# Ananas-core-0_9_2.net
KiCad netlist of a schematic drawn in EAGLE
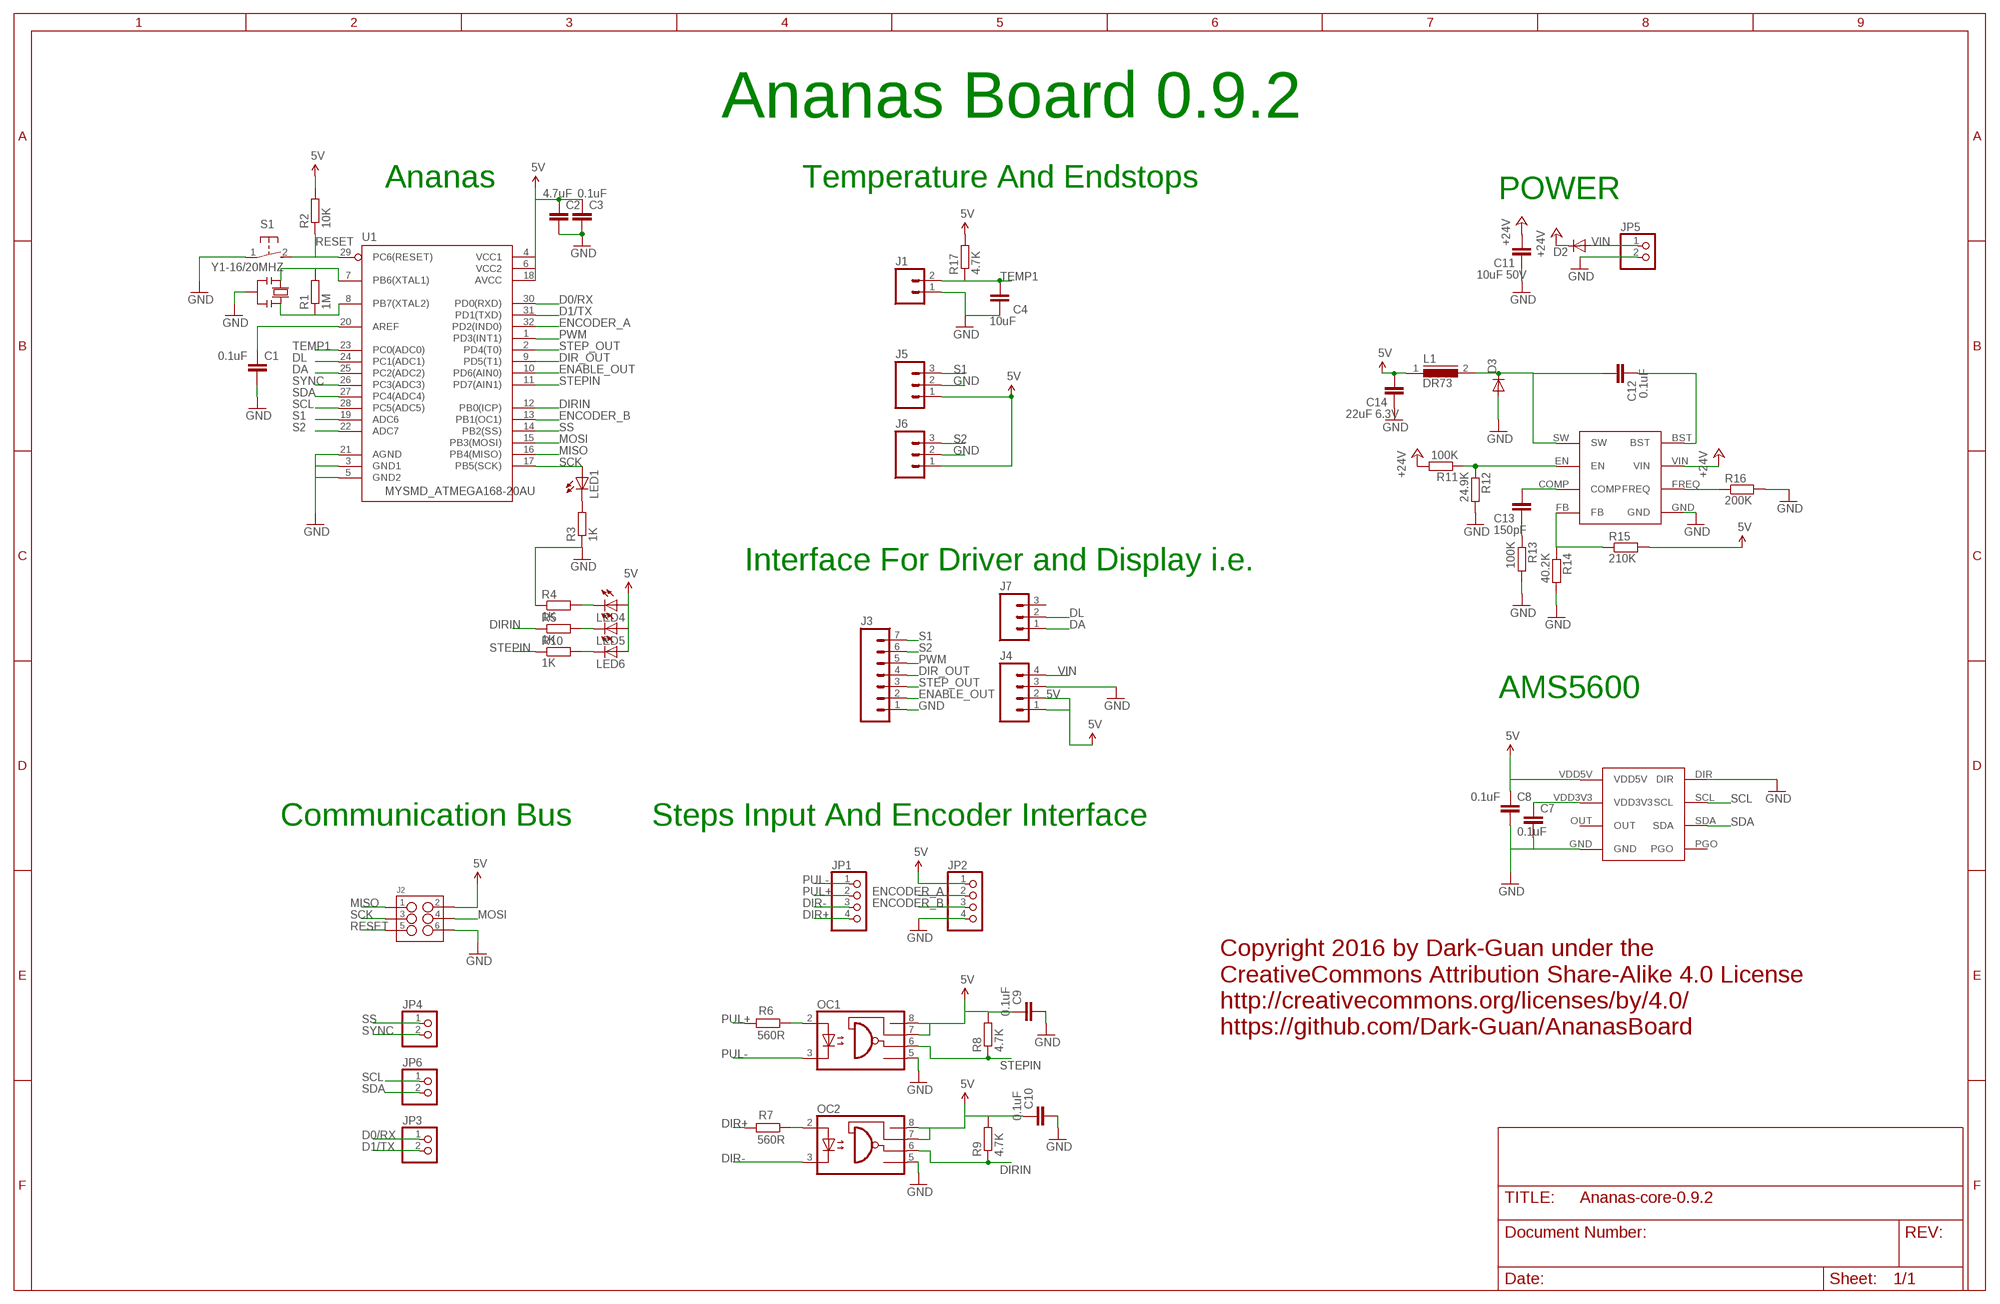
[diagram p0: schematic, sheet 1]

(export (version "E")
  (design (tool "Eeschema 10.0.6"))
  (components
    (comp (ref "C1")
      (value "0.1uF")
      (footprint "eagle-import:C0603K")
      (libsource (lib "eagle-import") (part "C-EUC0603K"))
    )
    (comp (ref "C2")
      (value "4.7uF")
      (footprint "eagle-import:C0603K")
      (libsource (lib "eagle-import") (part "C-EUC0603K"))
    )
    (comp (ref "C3")
      (value "0.1uF")
      (footprint "eagle-import:C0603K")
      (libsource (lib "eagle-import") (part "C-EUC0603K"))
    )
    (comp (ref "C4")
      (value "10uF")
      (footprint "eagle-import:C0603K")
      (libsource (lib "eagle-import") (part "C-EUC0603K"))
    )
    (comp (ref "C7")
      (value "0.1uF")
      (footprint "eagle-import:C0603K")
      (libsource (lib "eagle-import") (part "C-EUC0603K"))
    )
    (comp (ref "C8")
      (value "0.1uF")
      (footprint "eagle-import:C0603K")
      (libsource (lib "eagle-import") (part "C-EUC0603K"))
    )
    (comp (ref "C9")
      (value "0.1uF")
      (footprint "eagle-import:C0603K")
      (libsource (lib "eagle-import") (part "C-EUC0603K"))
    )
    (comp (ref "C10")
      (value "0.1uF")
      (footprint "eagle-import:C0603K")
      (libsource (lib "eagle-import") (part "C-EUC0603K"))
    )
    (comp (ref "C11")
      (value "10uF 50V")
      (footprint "eagle-import:C0805")
      (libsource (lib "eagle-import") (part "C-EUC0805"))
    )
    (comp (ref "C12")
      (value "0.1uF")
      (footprint "eagle-import:C0603K")
      (libsource (lib "eagle-import") (part "C-EUC0603K"))
    )
    (comp (ref "C13")
      (value "150pF")
      (footprint "eagle-import:C0603K")
      (libsource (lib "eagle-import") (part "C-EUC0603K"))
    )
    (comp (ref "C14")
      (value "22uF 6.3V")
      (footprint "eagle-import:C0805")
      (libsource (lib "eagle-import") (part "C-EUC0805"))
    )
    (comp (ref "D2")
      (value "DIODE_DIODE-SMB")
      (footprint "eagle-import:DIODE_SMB")
      (libsource (lib "eagle-import") (part "DIODE_DIODE-SMB"))
    )
    (comp (ref "D3")
      (value "DIODE_DIODE-SMB")
      (footprint "eagle-import:DIODE_SMB")
      (libsource (lib "eagle-import") (part "DIODE_DIODE-SMB"))
    )
    (comp (ref "J1")
      (value "M02PTH")
      (footprint "eagle-import:1X02")
      (libsource (lib "eagle-import") (part "M02PTH"))
    )
    (comp (ref "J2")
      (value "M03X2NO_SILK")
      (footprint "eagle-import:2X3-NS")
      (libsource (lib "eagle-import") (part "M03X2NO_SILK"))
    )
    (comp (ref "J3")
      (value "M07")
      (footprint "eagle-import:1X07")
      (libsource (lib "eagle-import") (part "M07"))
    )
    (comp (ref "J4")
      (value "M04PTH")
      (footprint "eagle-import:1X04")
      (libsource (lib "eagle-import") (part "M04PTH"))
    )
    (comp (ref "J5")
      (value "M03PTH")
      (footprint "eagle-import:1X03")
      (libsource (lib "eagle-import") (part "M03PTH"))
    )
    (comp (ref "J6")
      (value "M03PTH")
      (footprint "eagle-import:1X03")
      (libsource (lib "eagle-import") (part "M03PTH"))
    )
    (comp (ref "J7")
      (value "M03PTH")
      (footprint "eagle-import:1X03")
      (libsource (lib "eagle-import") (part "M03PTH"))
    )
    (comp (ref "JP1")
      (value "PINHD-1X4/OCT")
      (footprint "eagle-import:1X04_OCT")
      (libsource (lib "eagle-import") (part "PINHD-1X4/OCT"))
    )
    (comp (ref "JP2")
      (value "PINHD-1X4/OCT")
      (footprint "eagle-import:1X04_OCT")
      (libsource (lib "eagle-import") (part "PINHD-1X4/OCT"))
    )
    (comp (ref "JP3")
      (value "PINHD-1X2/OCT")
      (footprint "eagle-import:1X02_OCT")
      (libsource (lib "eagle-import") (part "PINHD-1X2/OCT"))
    )
    (comp (ref "JP4")
      (value "PINHD-1X2/OCT")
      (footprint "eagle-import:1X02_OCT")
      (libsource (lib "eagle-import") (part "PINHD-1X2/OCT"))
    )
    (comp (ref "JP5")
      (value "PINHD-1X2/OCT")
      (footprint "eagle-import:1X02_OCT")
      (libsource (lib "eagle-import") (part "PINHD-1X2/OCT"))
    )
    (comp (ref "JP6")
      (value "PINHD-1X2/OCT")
      (footprint "eagle-import:1X02_OCT")
      (libsource (lib "eagle-import") (part "PINHD-1X2/OCT"))
    )
    (comp (ref "L1")
      (value "DR73")
      (footprint "eagle-import:DR73")
      (libsource (lib "eagle-import") (part "DR73"))
    )
    (comp (ref "LED1")
      (value "LEDCHIPLED_0603")
      (footprint "eagle-import:CHIPLED_0603")
      (libsource (lib "eagle-import") (part "LEDCHIPLED_0603"))
    )
    (comp (ref "LED4")
      (value "LEDCHIPLED_0603")
      (footprint "eagle-import:CHIPLED_0603")
      (libsource (lib "eagle-import") (part "LEDCHIPLED_0603"))
    )
    (comp (ref "LED5")
      (value "LEDCHIPLED_0603")
      (footprint "eagle-import:CHIPLED_0603")
      (libsource (lib "eagle-import") (part "LEDCHIPLED_0603"))
    )
    (comp (ref "LED6")
      (value "LEDCHIPLED_0603")
      (footprint "eagle-import:CHIPLED_0603")
      (libsource (lib "eagle-import") (part "LEDCHIPLED_0603"))
    )
    (comp (ref "MP1854")
      (value "MP1584")
      (footprint "eagle-import:MP1584")
      (libsource (lib "eagle-import") (part "MP1584"))
    )
    (comp (ref "OC1")
      (value "OPTOCOUPLER_(2)_HCPL0600")
      (footprint "eagle-import:OPTOCOUPLER_(2)_SOIC08")
      (libsource (lib "eagle-import") (part "OPTOCOUPLER_(2)_HCPL0600"))
    )
    (comp (ref "OC2")
      (value "OPTOCOUPLER_(2)_HCPL0600")
      (footprint "eagle-import:OPTOCOUPLER_(2)_SOIC08")
      (libsource (lib "eagle-import") (part "OPTOCOUPLER_(2)_HCPL0600"))
    )
    (comp (ref "R1")
      (value "1M")
      (footprint "eagle-import:R0603")
      (libsource (lib "eagle-import") (part "R-EU_R0603"))
    )
    (comp (ref "R2")
      (value "10K")
      (footprint "eagle-import:R0603")
      (libsource (lib "eagle-import") (part "R-EU_R0603"))
    )
    (comp (ref "R3")
      (value "1K")
      (footprint "eagle-import:R0603")
      (libsource (lib "eagle-import") (part "R-EU_R0603"))
    )
    (comp (ref "R4")
      (value "1K")
      (footprint "eagle-import:R0603")
      (libsource (lib "eagle-import") (part "R-EU_R0603"))
    )
    (comp (ref "R5")
      (value "1K")
      (footprint "eagle-import:R0603")
      (libsource (lib "eagle-import") (part "R-EU_R0603"))
    )
    (comp (ref "R6")
      (value "560R")
      (footprint "eagle-import:R0603")
      (libsource (lib "eagle-import") (part "R-EU_R0603"))
    )
    (comp (ref "R7")
      (value "560R")
      (footprint "eagle-import:R0603")
      (libsource (lib "eagle-import") (part "R-EU_R0603"))
    )
    (comp (ref "R8")
      (value "4.7K")
      (footprint "eagle-import:R0603")
      (libsource (lib "eagle-import") (part "R-EU_R0603"))
    )
    (comp (ref "R9")
      (value "4.7K")
      (footprint "eagle-import:R0603")
      (libsource (lib "eagle-import") (part "R-EU_R0603"))
    )
    (comp (ref "R10")
      (value "1K")
      (footprint "eagle-import:R0603")
      (libsource (lib "eagle-import") (part "R-EU_R0603"))
    )
    (comp (ref "R11")
      (value "100K")
      (footprint "eagle-import:R0603")
      (libsource (lib "eagle-import") (part "R-EU_R0603"))
    )
    (comp (ref "R12")
      (value "24.9K")
      (footprint "eagle-import:R0603")
      (libsource (lib "eagle-import") (part "R-EU_R0603"))
    )
    (comp (ref "R13")
      (value "100K")
      (footprint "eagle-import:R0603")
      (libsource (lib "eagle-import") (part "R-EU_R0603"))
    )
    (comp (ref "R14")
      (value "40.2K")
      (footprint "eagle-import:R0603")
      (libsource (lib "eagle-import") (part "R-EU_R0603"))
    )
    (comp (ref "R15")
      (value "210K")
      (footprint "eagle-import:R0603")
      (libsource (lib "eagle-import") (part "R-EU_R0603"))
    )
    (comp (ref "R16")
      (value "200K")
      (footprint "eagle-import:R0603")
      (libsource (lib "eagle-import") (part "R-EU_R0603"))
    )
    (comp (ref "R17")
      (value "4.7K")
      (footprint "eagle-import:R0603")
      (libsource (lib "eagle-import") (part "R-EU_R0603"))
    )
    (comp (ref "S1")
      (value "31-XX")
      (footprint "eagle-import:B3F-31XX")
      (fields (field (name "MPN") "B3F-3100"))
      (libsource (lib "eagle-import") (part "31-XX"))
    )
    (comp (ref "U$1")
      (value "ARDUINO_AS5600")
      (footprint "eagle-import:ARDUINO_AS5600")
      (libsource (lib "eagle-import") (part "ARDUINO_AS5600"))
    )
    (comp (ref "U1")
      (value "MYSMD_ATMEGA168-20AU")
      (footprint "eagle-import:MYSMD_QFP032")
      (libsource (lib "eagle-import") (part "MYSMD_ATMEGA168-20AU"))
    )
    (comp (ref "Y1-16/20MHZ")
      (value "MYSMD2_RESONATORMU")
      (footprint "eagle-import:MYSMD2_RESONATOR")
      (libsource (lib "eagle-import") (part "MYSMD2_RESONATORMU"))
    )
  )
  (nets
    (net (code "1") (name "+24V") (class "Default")
      (node (ref "C11") (pin "2") (pinfunction "2_2") (pintype "passive"))
      (node (ref "D2") (pin "C") (pinfunction "C_C") (pintype "passive"))
      (node (ref "MP1854") (pin "VIN") (pinfunction "VIN_VIN") (pintype "bidirectional"))
      (node (ref "R11") (pin "2") (pinfunction "2_2") (pintype "passive"))
    )
    (net (code "2") (name "/D0{slash}RX") (class "Default")
      (node (ref "JP3") (pin "1") (pinfunction "1_1") (pintype "passive"))
      (node (ref "U1") (pin "30") (pinfunction "PD0(RXD)_30") (pintype "bidirectional"))
    )
    (net (code "3") (name "/D1{slash}TX") (class "Default")
      (node (ref "JP3") (pin "2") (pinfunction "2_2") (pintype "passive"))
      (node (ref "U1") (pin "31") (pinfunction "PD1(TXD)_31") (pintype "bidirectional"))
    )
    (net (code "4") (name "/DA") (class "Default")
      (node (ref "J7") (pin "1") (pinfunction "1_1") (pintype "passive"))
      (node (ref "U1") (pin "25") (pinfunction "PC2(ADC2)_25") (pintype "passive"))
    )
    (net (code "5") (name "/DIR+") (class "Default")
      (node (ref "JP1") (pin "4") (pinfunction "4_4") (pintype "passive"))
      (node (ref "R7") (pin "2") (pinfunction "2_2") (pintype "passive"))
    )
    (net (code "6") (name "/DIR-") (class "Default")
      (node (ref "JP1") (pin "3") (pinfunction "3_3") (pintype "passive"))
      (node (ref "OC2") (pin "3") (pinfunction "C_3") (pintype "passive"))
    )
    (net (code "7") (name "/DIRIN") (class "Default")
      (node (ref "OC2") (pin "6") (pinfunction "VO_6") (pintype "passive"))
      (node (ref "R5") (pin "1") (pinfunction "1_1") (pintype "passive"))
      (node (ref "R9") (pin "1") (pinfunction "1_1") (pintype "passive"))
      (node (ref "U1") (pin "12") (pinfunction "PB0(ICP)_12") (pintype "bidirectional"))
    )
    (net (code "8") (name "/DIR_OUT") (class "Default")
      (node (ref "J3") (pin "4") (pinfunction "4_4") (pintype "passive"))
      (node (ref "U1") (pin "9") (pinfunction "PD5(T1)_9") (pintype "bidirectional"))
    )
    (net (code "9") (name "/DL") (class "Default")
      (node (ref "J7") (pin "2") (pinfunction "2_2") (pintype "passive"))
      (node (ref "U1") (pin "24") (pinfunction "PC1(ADC1)_24") (pintype "passive"))
    )
    (net (code "10") (name "/ENABLE_OUT") (class "Default")
      (node (ref "J3") (pin "2") (pinfunction "2_2") (pintype "passive"))
      (node (ref "U1") (pin "10") (pinfunction "PD6(AIN0)_10") (pintype "bidirectional"))
    )
    (net (code "11") (name "/ENCODER_A") (class "Default")
      (node (ref "JP2") (pin "2") (pinfunction "2_2") (pintype "passive"))
      (node (ref "U1") (pin "32") (pinfunction "PD2(IND0)_32") (pintype "bidirectional"))
    )
    (net (code "12") (name "/ENCODER_B") (class "Default")
      (node (ref "JP2") (pin "3") (pinfunction "3_3") (pintype "passive"))
      (node (ref "U1") (pin "13") (pinfunction "PB1(OC1)_13") (pintype "bidirectional"))
    )
    (net (code "13") (name "/MISO") (class "Default")
      (node (ref "J2") (pin "1") (pinfunction "1_1") (pintype "bidirectional"))
      (node (ref "U1") (pin "16") (pinfunction "PB4(MISO)_16") (pintype "bidirectional"))
    )
    (net (code "14") (name "/MOSI") (class "Default")
      (node (ref "J2") (pin "4") (pinfunction "4_4") (pintype "bidirectional"))
      (node (ref "U1") (pin "15") (pinfunction "PB3(MOSI)_15") (pintype "bidirectional"))
    )
    (net (code "15") (name "/PUL+") (class "Default")
      (node (ref "JP1") (pin "2") (pinfunction "2_2") (pintype "passive"))
      (node (ref "R6") (pin "2") (pinfunction "2_2") (pintype "passive"))
    )
    (net (code "16") (name "/PUL-") (class "Default")
      (node (ref "JP1") (pin "1") (pinfunction "1_1") (pintype "passive"))
      (node (ref "OC1") (pin "3") (pinfunction "C_3") (pintype "passive"))
    )
    (net (code "17") (name "/PWM") (class "Default")
      (node (ref "J3") (pin "5") (pinfunction "5_5") (pintype "passive"))
      (node (ref "U1") (pin "1") (pinfunction "PD3(INT1)_1") (pintype "bidirectional"))
    )
    (net (code "18") (name "/RESET") (class "Default")
      (node (ref "J2") (pin "5") (pinfunction "5_5") (pintype "bidirectional"))
      (node (ref "R2") (pin "1") (pinfunction "1_1") (pintype "passive"))
      (node (ref "S1") (pin "2") (pinfunction "S_2") (pintype "passive"))
      (node (ref "U1") (pin "29") (pinfunction "PC6(RESET)_29") (pintype "bidirectional"))
    )
    (net (code "19") (name "/S1") (class "Default")
      (node (ref "J3") (pin "7") (pinfunction "7_7") (pintype "passive"))
      (node (ref "J5") (pin "3") (pinfunction "3_3") (pintype "passive"))
      (node (ref "U1") (pin "19") (pinfunction "ADC6_19") (pintype "passive"))
    )
    (net (code "20") (name "/S2") (class "Default")
      (node (ref "J3") (pin "6") (pinfunction "6_6") (pintype "passive"))
      (node (ref "J6") (pin "3") (pinfunction "3_3") (pintype "passive"))
      (node (ref "U1") (pin "22") (pinfunction "ADC7_22") (pintype "passive"))
    )
    (net (code "21") (name "/SCK") (class "Default")
      (node (ref "J2") (pin "3") (pinfunction "3_3") (pintype "bidirectional"))
      (node (ref "LED1") (pin "A") (pinfunction "A_A") (pintype "passive"))
      (node (ref "U1") (pin "17") (pinfunction "PB5(SCK)_17") (pintype "bidirectional"))
    )
    (net (code "22") (name "/SCL") (class "Default")
      (node (ref "JP6") (pin "1") (pinfunction "1_1") (pintype "passive"))
      (node (ref "U$1") (pin "SCL") (pinfunction "SCL_SCL") (pintype "bidirectional"))
      (node (ref "U1") (pin "28") (pinfunction "PC5(ADC5)_28") (pintype "passive"))
    )
    (net (code "23") (name "/SDA") (class "Default")
      (node (ref "JP6") (pin "2") (pinfunction "2_2") (pintype "passive"))
      (node (ref "U$1") (pin "SDA") (pinfunction "SDA_SDA") (pintype "bidirectional"))
      (node (ref "U1") (pin "27") (pinfunction "PC4(ADC4)_27") (pintype "passive"))
    )
    (net (code "24") (name "/SS") (class "Default")
      (node (ref "JP4") (pin "1") (pinfunction "1_1") (pintype "passive"))
      (node (ref "U1") (pin "14") (pinfunction "PB2(SS)_14") (pintype "bidirectional"))
    )
    (net (code "25") (name "/STEPIN") (class "Default")
      (node (ref "OC1") (pin "6") (pinfunction "VO_6") (pintype "passive"))
      (node (ref "R10") (pin "1") (pinfunction "1_1") (pintype "passive"))
      (node (ref "R8") (pin "1") (pinfunction "1_1") (pintype "passive"))
      (node (ref "U1") (pin "11") (pinfunction "PD7(AIN1)_11") (pintype "bidirectional"))
    )
    (net (code "26") (name "/STEP_OUT") (class "Default")
      (node (ref "J3") (pin "3") (pinfunction "3_3") (pintype "passive"))
      (node (ref "U1") (pin "2") (pinfunction "PD4(T0)_2") (pintype "bidirectional"))
    )
    (net (code "27") (name "/SYNC") (class "Default")
      (node (ref "JP4") (pin "2") (pinfunction "2_2") (pintype "passive"))
      (node (ref "U1") (pin "26") (pinfunction "PC3(ADC3)_26") (pintype "passive"))
    )
    (net (code "28") (name "/TEMP1") (class "Default")
      (node (ref "C4") (pin "2") (pinfunction "2_2") (pintype "passive"))
      (node (ref "J1") (pin "2") (pinfunction "2_2") (pintype "passive"))
      (node (ref "R17") (pin "1") (pinfunction "1_1") (pintype "passive"))
      (node (ref "U1") (pin "23") (pinfunction "PC0(ADC0)_23") (pintype "passive"))
    )
    (net (code "29") (name "/VIN") (class "Default")
      (node (ref "D2") (pin "A") (pinfunction "A_A") (pintype "passive"))
      (node (ref "J4") (pin "4") (pinfunction "4_4") (pintype "passive"))
      (node (ref "JP5") (pin "1") (pinfunction "1_1") (pintype "passive"))
    )
    (net (code "30") (name "5V") (class "Default")
      (node (ref "C10") (pin "1") (pinfunction "1_1") (pintype "passive"))
      (node (ref "C14") (pin "2") (pinfunction "2_2") (pintype "passive"))
      (node (ref "C2") (pin "1") (pinfunction "1_1") (pintype "passive"))
      (node (ref "C3") (pin "1") (pinfunction "1_1") (pintype "passive"))
      (node (ref "C8") (pin "1") (pinfunction "1_1") (pintype "passive"))
      (node (ref "C9") (pin "1") (pinfunction "1_1") (pintype "passive"))
      (node (ref "J2") (pin "2") (pinfunction "2_2") (pintype "bidirectional"))
      (node (ref "J4") (pin "1") (pinfunction "1_1") (pintype "passive"))
      (node (ref "J4") (pin "2") (pinfunction "2_2") (pintype "passive"))
      (node (ref "J5") (pin "1") (pinfunction "1_1") (pintype "passive"))
      (node (ref "J6") (pin "1") (pinfunction "1_1") (pintype "passive"))
      (node (ref "JP2") (pin "1") (pinfunction "1_1") (pintype "passive"))
      (node (ref "L1") (pin "1") (pinfunction "1_1") (pintype "passive"))
      (node (ref "LED4") (pin "A") (pinfunction "A_A") (pintype "passive"))
      (node (ref "LED5") (pin "A") (pinfunction "A_A") (pintype "passive"))
      (node (ref "LED6") (pin "A") (pinfunction "A_A") (pintype "passive"))
      (node (ref "OC1") (pin "7") (pinfunction "VE_7") (pintype "passive"))
      (node (ref "OC1") (pin "8") (pinfunction "VCC_8") (pintype "passive"))
      (node (ref "OC2") (pin "7") (pinfunction "VE_7") (pintype "passive"))
      (node (ref "OC2") (pin "8") (pinfunction "VCC_8") (pintype "passive"))
      (node (ref "R15") (pin "2") (pinfunction "2_2") (pintype "passive"))
      (node (ref "R17") (pin "2") (pinfunction "2_2") (pintype "passive"))
      (node (ref "R2") (pin "2") (pinfunction "2_2") (pintype "passive"))
      (node (ref "R8") (pin "2") (pinfunction "2_2") (pintype "passive"))
      (node (ref "R9") (pin "2") (pinfunction "2_2") (pintype "passive"))
      (node (ref "U$1") (pin "VDD5V") (pinfunction "VDD5V_VDD5V") (pintype "bidirectional"))
      (node (ref "U1") (pin "18") (pinfunction "AVCC_18") (pintype "passive"))
      (node (ref "U1") (pin "4") (pinfunction "VCC1_4") (pintype "power_in"))
      (node (ref "U1") (pin "6") (pinfunction "VCC2_6") (pintype "power_in"))
    )
    (net (code "31") (name "GND") (class "Default")
      (node (ref "C1") (pin "2") (pinfunction "2_2") (pintype "passive"))
      (node (ref "C10") (pin "2") (pinfunction "2_2") (pintype "passive"))
      (node (ref "C11") (pin "1") (pinfunction "1_1") (pintype "passive"))
      (node (ref "C14") (pin "1") (pinfunction "1_1") (pintype "passive"))
      (node (ref "C2") (pin "2") (pinfunction "2_2") (pintype "passive"))
      (node (ref "C3") (pin "2") (pinfunction "2_2") (pintype "passive"))
      (node (ref "C4") (pin "1") (pinfunction "1_1") (pintype "passive"))
      (node (ref "C7") (pin "2") (pinfunction "2_2") (pintype "passive"))
      (node (ref "C8") (pin "2") (pinfunction "2_2") (pintype "passive"))
      (node (ref "C9") (pin "2") (pinfunction "2_2") (pintype "passive"))
      (node (ref "D3") (pin "A") (pinfunction "A_A") (pintype "passive"))
      (node (ref "J1") (pin "1") (pinfunction "1_1") (pintype "passive"))
      (node (ref "J2") (pin "6") (pinfunction "6_6") (pintype "bidirectional"))
      (node (ref "J3") (pin "1") (pinfunction "1_1") (pintype "passive"))
      (node (ref "J4") (pin "3") (pinfunction "3_3") (pintype "passive"))
      (node (ref "J5") (pin "2") (pinfunction "2_2") (pintype "passive"))
      (node (ref "J6") (pin "2") (pinfunction "2_2") (pintype "passive"))
      (node (ref "JP2") (pin "4") (pinfunction "4_4") (pintype "passive"))
      (node (ref "JP5") (pin "2") (pinfunction "2_2") (pintype "passive"))
      (node (ref "MP1854") (pin "GND") (pinfunction "GND_GND") (pintype "bidirectional"))
      (node (ref "OC1") (pin "5") (pinfunction "GND_5") (pintype "passive"))
      (node (ref "OC2") (pin "5") (pinfunction "GND_5") (pintype "passive"))
      (node (ref "R12") (pin "2") (pinfunction "2_2") (pintype "passive"))
      (node (ref "R13") (pin "2") (pinfunction "2_2") (pintype "passive"))
      (node (ref "R14") (pin "2") (pinfunction "2_2") (pintype "passive"))
      (node (ref "R16") (pin "2") (pinfunction "2_2") (pintype "passive"))
      (node (ref "R3") (pin "1") (pinfunction "1_1") (pintype "passive"))
      (node (ref "R4") (pin "1") (pinfunction "1_1") (pintype "passive"))
      (node (ref "S1") (pin "1") (pinfunction "P_1") (pintype "passive"))
      (node (ref "U$1") (pin "DIR") (pinfunction "DIR_DIR") (pintype "bidirectional"))
      (node (ref "U$1") (pin "GND") (pinfunction "GND_GND") (pintype "bidirectional"))
      (node (ref "U1") (pin "21") (pinfunction "AGND_21") (pintype "passive"))
      (node (ref "U1") (pin "3") (pinfunction "GND1_3") (pintype "power_in"))
      (node (ref "U1") (pin "5") (pinfunction "GND2_5") (pintype "power_in"))
      (node (ref "Y1-16/20MHZ") (pin "2") (pinfunction "2_2") (pintype "passive"))
    )
    (net (code "32") (name "Net-(C7-Pad1)") (class "Default")
      (node (ref "C7") (pin "1") (pinfunction "1_1") (pintype "passive"))
      (node (ref "U$1") (pin "VDD3V3") (pinfunction "VDD3V3_VDD3V3") (pintype "bidirectional"))
    )
    (net (code "33") (name "Net-(C12-Pad1)") (class "Default")
      (node (ref "C12") (pin "1") (pinfunction "1_1") (pintype "passive"))
      (node (ref "MP1854") (pin "BST") (pinfunction "BST_BST") (pintype "bidirectional"))
    )
    (net (code "34") (name "Net-(C12-Pad2)") (class "Default")
      (node (ref "C12") (pin "2") (pinfunction "2_2") (pintype "passive"))
      (node (ref "D3") (pin "C") (pinfunction "C_C") (pintype "passive"))
      (node (ref "L1") (pin "2") (pinfunction "2_2") (pintype "passive"))
      (node (ref "MP1854") (pin "SW") (pinfunction "SW_SW") (pintype "bidirectional"))
    )
    (net (code "35") (name "Net-(C13-Pad1)") (class "Default")
      (node (ref "C13") (pin "1") (pinfunction "1_1") (pintype "passive"))
      (node (ref "R13") (pin "1") (pinfunction "1_1") (pintype "passive"))
    )
    (net (code "36") (name "Net-(C13-Pad2)") (class "Default")
      (node (ref "C13") (pin "2") (pinfunction "2_2") (pintype "passive"))
      (node (ref "MP1854") (pin "COMP") (pinfunction "COMP_COMP") (pintype "bidirectional"))
    )
    (net (code "37") (name "Net-(LED1-PadC)") (class "Default")
      (node (ref "LED1") (pin "C") (pinfunction "C_C") (pintype "passive"))
      (node (ref "R3") (pin "2") (pinfunction "2_2") (pintype "passive"))
    )
    (net (code "38") (name "Net-(LED4-PadC)") (class "Default")
      (node (ref "LED4") (pin "C") (pinfunction "C_C") (pintype "passive"))
      (node (ref "R4") (pin "2") (pinfunction "2_2") (pintype "passive"))
    )
    (net (code "39") (name "Net-(LED5-PadC)") (class "Default")
      (node (ref "LED5") (pin "C") (pinfunction "C_C") (pintype "passive"))
      (node (ref "R5") (pin "2") (pinfunction "2_2") (pintype "passive"))
    )
    (net (code "40") (name "Net-(LED6-PadC)") (class "Default")
      (node (ref "LED6") (pin "C") (pinfunction "C_C") (pintype "passive"))
      (node (ref "R10") (pin "2") (pinfunction "2_2") (pintype "passive"))
    )
    (net (code "41") (name "Net-(MP1854-PadEN)") (class "Default")
      (node (ref "MP1854") (pin "EN") (pinfunction "EN_EN") (pintype "bidirectional"))
      (node (ref "R11") (pin "1") (pinfunction "1_1") (pintype "passive"))
      (node (ref "R12") (pin "1") (pinfunction "1_1") (pintype "passive"))
    )
    (net (code "42") (name "Net-(MP1854-PadFB)") (class "Default")
      (node (ref "MP1854") (pin "FB") (pinfunction "FB_FB") (pintype "bidirectional"))
      (node (ref "R14") (pin "1") (pinfunction "1_1") (pintype "passive"))
      (node (ref "R15") (pin "1") (pinfunction "1_1") (pintype "passive"))
    )
    (net (code "43") (name "Net-(MP1854-PadFREQ)") (class "Default")
      (node (ref "MP1854") (pin "FREQ") (pinfunction "FREQ_FREQ") (pintype "bidirectional"))
      (node (ref "R16") (pin "1") (pinfunction "1_1") (pintype "passive"))
    )
    (net (code "44") (name "Net-(OC1-A)") (class "Default")
      (node (ref "OC1") (pin "2") (pinfunction "A_2") (pintype "passive"))
      (node (ref "R6") (pin "1") (pinfunction "1_1") (pintype "passive"))
    )
    (net (code "45") (name "Net-(OC2-A)") (class "Default")
      (node (ref "OC2") (pin "2") (pinfunction "A_2") (pintype "passive"))
      (node (ref "R7") (pin "1") (pinfunction "1_1") (pintype "passive"))
    )
    (net (code "46") (name "Net-(U1-AREF)") (class "Default")
      (node (ref "C1") (pin "1") (pinfunction "1_1") (pintype "passive"))
      (node (ref "U1") (pin "20") (pinfunction "AREF_20") (pintype "passive"))
    )
    (net (code "47") (name "Net-(U1-PB6(XTAL1))") (class "Default")
      (node (ref "R1") (pin "2") (pinfunction "2_2") (pintype "passive"))
      (node (ref "U1") (pin "7") (pinfunction "PB6(XTAL1)_7") (pintype "passive"))
      (node (ref "Y1-16/20MHZ") (pin "1") (pinfunction "1_1") (pintype "passive"))
    )
    (net (code "48") (name "Net-(U1-PB7(XTAL2))") (class "Default")
      (node (ref "R1") (pin "1") (pinfunction "1_1") (pintype "passive"))
      (node (ref "U1") (pin "8") (pinfunction "PB7(XTAL2)_8") (pintype "passive"))
      (node (ref "Y1-16/20MHZ") (pin "3") (pinfunction "3_3") (pintype "passive"))
    )
    (net (code "49") (name "unconnected-(J7-Pad3)") (class "Default")
      (node (ref "J7") (pin "3") (pinfunction "3_3") (pintype "passive"))
    )
    (net (code "50") (name "unconnected-(U$1-PadOUT)") (class "Default")
      (node (ref "U$1") (pin "OUT") (pinfunction "OUT_OUT") (pintype "bidirectional"))
    )
    (net (code "51") (name "unconnected-(U$1-PadPGO)") (class "Default")
      (node (ref "U$1") (pin "PGO") (pinfunction "PGO_PGO") (pintype "bidirectional"))
    )
  )
)
